# IsoPowerSupply.net
KiCad netlist of a schematic drawn in Altium Designer
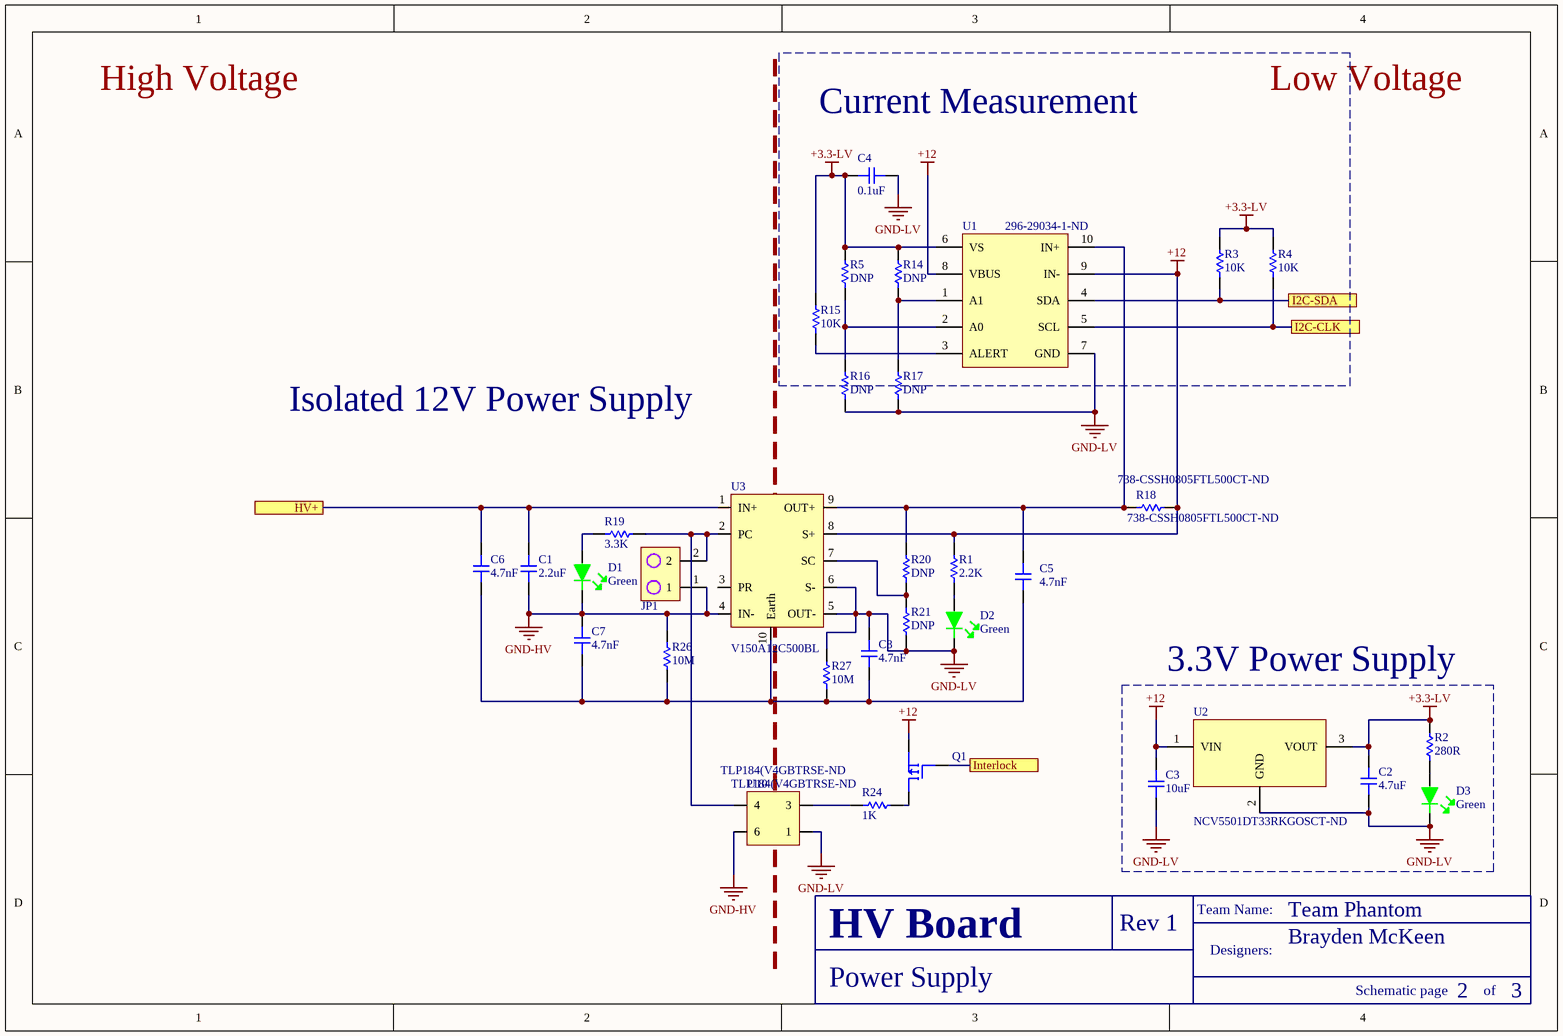
[diagram p0: IsoPowerSupply.SchDoc]

(export (version "E")
  (design (tool "Eeschema 10.0.6"))
  (components
    (comp (ref "C1")
      (value "2.2uF")
      (footprint "CAP-2220")
      (description "CAP CER 2.2UF 450V X6S 2220")
      (fields
        (field (name "MANUFACTURER") "TDK")
        (field (name "MANUFACTURER PART NUMBER") "C5750X6S2W225K250KA")
      )
      (libsource (lib "Capacitors") (part "2220-2.2uF-450V"))
    )
    (comp (ref "C2")
      (value "4.7uF")
      (footprint "CAP-0805")
      (description "CAP CER 4.7UF 16V X5R 0805")
      (fields
        (field (name "MANUFACTURER") "KEMET")
        (field (name "MANUFACTURER PART NUMBER") "C0805C475K4PACTU")
      )
      (libsource (lib "Capacitors") (part "0805-4.7uF-16V"))
    )
    (comp (ref "C3")
      (value "10uF")
      (footprint "CAP-1206")
      (description "CAP CER 10UF 50V X5R 1206")
      (fields
        (field (name "MANUFACTURER") "Murata")
        (field (name "MANUFACTURER PART NUMBER") "GRT31CR61H106ME01L")
      )
      (libsource (lib "Capacitors") (part "1206-10uF-50V"))
    )
    (comp (ref "C4")
      (value "0.1uF")
      (footprint "CAP-0805")
      (description "CAP CER 0.1UF 16V Y5V 0805")
      (fields
        (field (name "MANUFACTURER") "KEMET")
        (field (name "MANUFACTURER PART NUMBER") "C0805C104Z4VACTU")
      )
      (libsource (lib "Capacitors") (part "0805-0.1uF-16V"))
    )
    (comp (ref "C5")
      (value "4.7nF")
      (footprint "CAP-0805")
      (description "CAP CER 4700PF 250V X7R 0805")
      (libsource (lib "Capacitors") (part "0805-4.7nF-250V"))
    )
    (comp (ref "C6")
      (value "4.7nF")
      (footprint "CAP-0805")
      (description "CAP CER 4700PF 250V X7R 0805")
      (libsource (lib "Capacitors") (part "0805-4.7nF-250V"))
    )
    (comp (ref "C7")
      (value "4.7nF")
      (footprint "CAP-0805")
      (description "CAP CER 4700PF 250V X7R 0805")
      (libsource (lib "Capacitors") (part "0805-4.7nF-250V"))
    )
    (comp (ref "C8")
      (value "4.7nF")
      (footprint "CAP-0805")
      (description "CAP CER 4700PF 250V X7R 0805")
      (libsource (lib "Capacitors") (part "0805-4.7nF-250V"))
    )
    (comp (ref "D1")
      (value "Green")
      (footprint "LED-0603")
      (description "LED GREEN CLEAR 0603 SMD")
      (fields
        (field (name "MANUFACTURER") "Wurth Electronics")
        (field (name "MANUFACTURER PART NUMBER") "150060VS75000")
      )
      (libsource (lib "LEDs") (part "LED-Green"))
    )
    (comp (ref "D2")
      (value "Green")
      (footprint "LED-0603")
      (description "LED GREEN CLEAR 0603 SMD")
      (fields
        (field (name "MANUFACTURER") "Wurth Electronics")
        (field (name "MANUFACTURER PART NUMBER") "150060VS75000")
      )
      (libsource (lib "LEDs") (part "LED-Green"))
    )
    (comp (ref "D3")
      (value "Green")
      (footprint "LED-0603")
      (description "LED GREEN CLEAR 0603 SMD")
      (fields
        (field (name "MANUFACTURER") "Wurth Electronics")
        (field (name "MANUFACTURER PART NUMBER") "150060VS75000")
      )
      (libsource (lib "LEDs") (part "LED-Green"))
    )
    (comp (ref "JP1")
      (value "732-5315-ND")
      (footprint "2PIN-JP")
      (description "CONN HEADER VERT 2POS 2.54MM")
      (libsource (lib "Connectors") (part "2PIN-TEST"))
    )
    (comp (ref "Q1")
      (value "448-ISS17EP06LMXTSA1CT-ND")
      (footprint "SOT-23-3")
      (description "MOSFET P-CH 60V 300MA SOT23-3")
      (fields
        (field (name "MANUFACTURER") "ON Semiconductor")
        (field (name "MANUFACTURER PART NUMBER") "ISS17EP06LMXTSA1")
      )
      (libsource (lib "Transistors") (part "P-FET-60V-0.3A"))
    )
    (comp (ref "R1")
      (value "2.2K")
      (footprint "RES-0805")
      (description "RES SMD 2.2K OHM 1% 1/8W 0805")
      (fields
        (field (name "MANUFACTURER") "Yageo")
        (field (name "MANUFACTURER PART NUMBER") "RC0805FR-072K2L")
      )
      (libsource (lib "Resistors") (part "0805-2.2KR"))
    )
    (comp (ref "R2")
      (value "280R")
      (footprint "RES-0805")
      (description "RES SMD 280 OHM 1% 1/8W 0805")
      (fields
        (field (name "MANUFACTURER") "Yageo")
        (field (name "MANUFACTURER PART NUMBER") "RC0805FR-07280RL")
      )
      (libsource (lib "Resistors") (part "0805-280R"))
    )
    (comp (ref "R3")
      (value "10K")
      (footprint "RES-0805")
      (description "RES SMD 10K OHM 1% 1/8W 0805")
      (fields
        (field (name "MANUFACTURER") "Yageo")
        (field (name "MANUFACTURER PART NUMBER") "RC0805FR-0710KL")
      )
      (libsource (lib "Resistors") (part "0805-10KR"))
    )
    (comp (ref "R4")
      (value "10K")
      (footprint "RES-0805")
      (description "RES SMD 10K OHM 1% 1/8W 0805")
      (fields
        (field (name "MANUFACTURER") "Yageo")
        (field (name "MANUFACTURER PART NUMBER") "RC0805FR-0710KL")
      )
      (libsource (lib "Resistors") (part "0805-10KR"))
    )
    (comp (ref "R5") (value "DNP") (footprint "RES-0805") (libsource (lib "Resistors") (part "DNP")))
    (comp (ref "R14") (value "DNP") (footprint "RES-0805") (libsource (lib "Resistors") (part "DNP")))
    (comp (ref "R15")
      (value "10K")
      (footprint "RES-0805")
      (description "RES SMD 10K OHM 1% 1/8W 0805")
      (fields
        (field (name "MANUFACTURER") "Yageo")
        (field (name "MANUFACTURER PART NUMBER") "RC0805FR-0710KL")
      )
      (libsource (lib "Resistors") (part "0805-10KR"))
    )
    (comp (ref "R16") (value "DNP") (footprint "RES-0805") (libsource (lib "Resistors") (part "DNP")))
    (comp (ref "R17") (value "DNP") (footprint "RES-0805") (libsource (lib "Resistors") (part "DNP")))
    (comp (ref "R18")
      (value "738-CSSH0805FTL500CT-ND")
      (footprint "RES-0805")
      (description "RES SHUNT, 0805, 0.0005 OHM, 1%,")
      (fields (field (name "SUPPLIER PART NUMBER 1") "738-CSSH0805FTL500CT-ND"))
      (libsource (lib "Resistors") (part "0805-0.0005R"))
    )
    (comp (ref "R19")
      (value "3.3K")
      (footprint "RES-0805")
      (description "RES SMD 3.3K OHM 1% 1/8W 0805")
      (fields
        (field (name "MANUFACTURER") "TE Connectivity")
        (field (name "MANUFACTURER PART NUMBER") "CRGCQ0805F3K3")
      )
      (libsource (lib "Resistors") (part "0805-3.3KR"))
    )
    (comp (ref "R20") (value "DNP") (footprint "RES-0805") (libsource (lib "Resistors") (part "DNP")))
    (comp (ref "R21") (value "DNP") (footprint "RES-0805") (libsource (lib "Resistors") (part "DNP")))
    (comp (ref "R24")
      (value "1K")
      (footprint "RES-0805")
      (description "RES SMD 1K OHM 1% 1/8W 0805")
      (fields
        (field (name "MANUFACTURER") "Yageo")
        (field (name "MANUFACTURER PART NUMBER") "RC0805FR-071KL")
      )
      (libsource (lib "Resistors") (part "0805-1KR"))
    )
    (comp (ref "R26")
      (value "10M")
      (footprint "RES-0805")
      (description "RES SMD 10M OHM 1% 1/8W 0805")
      (libsource (lib "Resistors") (part "0805-10MR"))
    )
    (comp (ref "R27")
      (value "10M")
      (footprint "RES-0805")
      (description "RES SMD 10M OHM 1% 1/8W 0805")
      (libsource (lib "Resistors") (part "0805-10MR"))
    )
    (comp (ref "U1")
      (value "296-29034-1-ND")
      (footprint "10MSOP")
      (description "IC MONITOR PWR/CURR BIDIR 10MSOP")
      (fields
        (field (name "MANUFACTURER") "Texas Instruments")
        (field (name "MANUFACTURER PART NUMBER") "INA226AIDGSR")
      )
      (libsource (lib "ICs") (part "PWR Monitor"))
    )
    (comp (ref "U2")
      (value "NCV5501DT33RKGOSCT-ND")
      (footprint "DPAK-TO252")
      (description "IC REG LINEAR 3.3V 500MA DPAK")
      (fields
        (field (name "MANUFACTURER") "ON Semiconductor")
        (field (name "MANUFACTURER PART NUMBER") "NCV5501DT33RKG")
      )
      (libsource (lib "Power") (part "LDO-3.3V-500mA"))
    )
    (comp (ref "U3")
      (value "V150A12C500BL")
      (footprint "DCDC-200V-12V-500W")
      (description "DC DC CONVERTER 12V 500W")
      (fields (field (name "MANUFACTURER") "Vicor"))
      (libsource (lib "Power") (part "DCDC200V-12V"))
    )
    (comp (ref "U10")
      (value "TLP184(V4GBTRSE-ND")
      (footprint "Photocoupler")
      (description "X36 PB-F PHOTOCOUPLER SO6 ROHS T")
      (fields (field (name "SUPPLIER PART NUMBER 1") "TLP184(V4GBTRSE-ND"))
      (libsource (lib "Misc") (part "Photocoupler"))
    )
  )
  (nets
    (net (code "1") (name "+3.3-LV") (class "Default")
      (node (ref "C2") (pin "2") (pinfunction "2_2") (pintype "passive"))
      (node (ref "C4") (pin "1") (pinfunction "1_1") (pintype "passive"))
      (node (ref "R14") (pin "2") (pinfunction "2_2") (pintype "passive"))
      (node (ref "R15") (pin "2") (pinfunction "2_2") (pintype "passive"))
      (node (ref "R2") (pin "2") (pinfunction "2_2") (pintype "passive"))
      (node (ref "R3") (pin "2") (pinfunction "2_2") (pintype "passive"))
      (node (ref "R4") (pin "2") (pinfunction "2_2") (pintype "passive"))
      (node (ref "R5") (pin "2") (pinfunction "2_2") (pintype "passive"))
      (node (ref "U1") (pin "6") (pinfunction "VS_6") (pintype "passive"))
      (node (ref "U2") (pin "3") (pinfunction "VOUT_3") (pintype "passive"))
    )
    (net (code "2") (name "+12") (class "Default")
      (node (ref "C3") (pin "2") (pinfunction "2_2") (pintype "passive"))
      (node (ref "Q1") (pin "2") (pinfunction "2_2") (pintype "passive"))
      (node (ref "R1") (pin "2") (pinfunction "2_2") (pintype "passive"))
      (node (ref "R18") (pin "2") (pinfunction "2_2") (pintype "passive"))
      (node (ref "U1") (pin "8") (pinfunction "VBUS_8") (pintype "passive"))
      (node (ref "U1") (pin "9") (pinfunction "IN-_9") (pintype "passive"))
      (node (ref "U2") (pin "1") (pinfunction "VIN_1") (pintype "passive"))
      (node (ref "U3") (pin "8") (pinfunction "S+_8") (pintype "passive"))
    )
    (net (code "3") (name "/HV+") (class "Default")
      (node (ref "C1") (pin "2") (pinfunction "2_2") (pintype "passive"))
      (node (ref "C6") (pin "2") (pinfunction "2_2") (pintype "passive"))
      (node (ref "U3") (pin "1") (pinfunction "IN+_1") (pintype "passive"))
    )
    (net (code "4") (name "/I2C-CLK") (class "Default")
      (node (ref "R4") (pin "1") (pinfunction "1_1") (pintype "passive"))
      (node (ref "U1") (pin "5") (pinfunction "SCL_5") (pintype "passive"))
    )
    (net (code "5") (name "/I2C-SDA") (class "Default")
      (node (ref "R3") (pin "1") (pinfunction "1_1") (pintype "passive"))
      (node (ref "U1") (pin "4") (pinfunction "SDA_4") (pintype "passive"))
    )
    (net (code "6") (name "/Interlock") (class "Default")
      (node (ref "Q1") (pin "1") (pinfunction "1_1") (pintype "passive"))
    )
    (net (code "7") (name "GND-HV") (class "Default")
      (node (ref "C1") (pin "1") (pinfunction "1_1") (pintype "passive"))
      (node (ref "C7") (pin "2") (pinfunction "2_2") (pintype "passive"))
      (node (ref "D1") (pin "2") (pinfunction "2_2") (pintype "passive"))
      (node (ref "JP1") (pin "1") (pinfunction "1_1") (pintype "passive"))
      (node (ref "R26") (pin "1") (pinfunction "1_1") (pintype "passive"))
      (node (ref "U10") (pin "6") (pinfunction "6_6") (pintype "passive"))
      (node (ref "U3") (pin "4") (pinfunction "IN-_4") (pintype "passive"))
    )
    (net (code "8") (name "GND-LV") (class "Default")
      (node (ref "C2") (pin "1") (pinfunction "1_1") (pintype "passive"))
      (node (ref "C3") (pin "1") (pinfunction "1_1") (pintype "passive"))
      (node (ref "C4") (pin "2") (pinfunction "2_2") (pintype "passive"))
      (node (ref "C8") (pin "2") (pinfunction "2_2") (pintype "passive"))
      (node (ref "D2") (pin "2") (pinfunction "2_2") (pintype "passive"))
      (node (ref "D3") (pin "2") (pinfunction "2_2") (pintype "passive"))
      (node (ref "R16") (pin "1") (pinfunction "1_1") (pintype "passive"))
      (node (ref "R17") (pin "1") (pinfunction "1_1") (pintype "passive"))
      (node (ref "R21") (pin "2") (pinfunction "2_2") (pintype "passive"))
      (node (ref "R27") (pin "2") (pinfunction "2_2") (pintype "passive"))
      (node (ref "U1") (pin "7") (pinfunction "GND_7") (pintype "passive"))
      (node (ref "U10") (pin "1") (pinfunction "1_1") (pintype "passive"))
      (node (ref "U2") (pin "2") (pinfunction "GND_2") (pintype "passive"))
      (node (ref "U3") (pin "5") (pinfunction "OUT-_5") (pintype "passive"))
      (node (ref "U3") (pin "6") (pinfunction "S-_6") (pintype "passive"))
    )
    (net (code "9") (name "Net-(D1-Pad1)") (class "Default")
      (node (ref "D1") (pin "1") (pinfunction "1_1") (pintype "passive"))
      (node (ref "R19") (pin "1") (pinfunction "1_1") (pintype "passive"))
    )
    (net (code "10") (name "Net-(D2-Pad1)") (class "Default")
      (node (ref "D2") (pin "1") (pinfunction "1_1") (pintype "passive"))
      (node (ref "R1") (pin "1") (pinfunction "1_1") (pintype "passive"))
    )
    (net (code "11") (name "Net-(D3-Pad1)") (class "Default")
      (node (ref "D3") (pin "1") (pinfunction "1_1") (pintype "passive"))
      (node (ref "R2") (pin "1") (pinfunction "1_1") (pintype "passive"))
    )
    (net (code "12") (name "Net-(Q1-Pad3)") (class "Default")
      (node (ref "Q1") (pin "3") (pinfunction "3_3") (pintype "passive"))
      (node (ref "R24") (pin "2") (pinfunction "2_2") (pintype "passive"))
    )
    (net (code "13") (name "Net-(R24-Pad1)") (class "Default")
      (node (ref "R24") (pin "1") (pinfunction "1_1") (pintype "passive"))
      (node (ref "U10") (pin "3") (pinfunction "3_3") (pintype "passive"))
    )
    (net (code "14") (name "Net-(U1-A0)") (class "Default")
      (node (ref "R16") (pin "2") (pinfunction "2_2") (pintype "passive"))
      (node (ref "R5") (pin "1") (pinfunction "1_1") (pintype "passive"))
      (node (ref "U1") (pin "2") (pinfunction "A0_2") (pintype "passive"))
    )
    (net (code "15") (name "Net-(U1-A1)") (class "Default")
      (node (ref "R14") (pin "1") (pinfunction "1_1") (pintype "passive"))
      (node (ref "R17") (pin "2") (pinfunction "2_2") (pintype "passive"))
      (node (ref "U1") (pin "1") (pinfunction "A1_1") (pintype "passive"))
    )
    (net (code "16") (name "Net-(U1-ALERT)") (class "Default")
      (node (ref "R15") (pin "1") (pinfunction "1_1") (pintype "passive"))
      (node (ref "U1") (pin "3") (pinfunction "ALERT_3") (pintype "passive"))
    )
    (net (code "17") (name "Net-(U1-IN+)") (class "Default")
      (node (ref "C5") (pin "2") (pinfunction "2_2") (pintype "passive"))
      (node (ref "R18") (pin "1") (pinfunction "1_1") (pintype "passive"))
      (node (ref "R20") (pin "2") (pinfunction "2_2") (pintype "passive"))
      (node (ref "U1") (pin "10") (pinfunction "IN+_10") (pintype "passive"))
      (node (ref "U3") (pin "9") (pinfunction "OUT+_9") (pintype "passive"))
    )
    (net (code "18") (name "Net-(U3-Earth)") (class "Default")
      (node (ref "C5") (pin "1") (pinfunction "1_1") (pintype "passive"))
      (node (ref "C6") (pin "1") (pinfunction "1_1") (pintype "passive"))
      (node (ref "C7") (pin "1") (pinfunction "1_1") (pintype "passive"))
      (node (ref "C8") (pin "1") (pinfunction "1_1") (pintype "passive"))
      (node (ref "R26") (pin "2") (pinfunction "2_2") (pintype "passive"))
      (node (ref "R27") (pin "1") (pinfunction "1_1") (pintype "passive"))
      (node (ref "U3") (pin "10") (pinfunction "Earth_10") (pintype "passive"))
    )
    (net (code "19") (name "Net-(U3-PC)") (class "Default")
      (node (ref "JP1") (pin "2") (pinfunction "2_2") (pintype "passive"))
      (node (ref "R19") (pin "2") (pinfunction "2_2") (pintype "passive"))
      (node (ref "U10") (pin "4") (pinfunction "4_4") (pintype "passive"))
      (node (ref "U3") (pin "2") (pinfunction "PC_2") (pintype "passive"))
    )
    (net (code "20") (name "Net-(U3-SC)") (class "Default")
      (node (ref "R20") (pin "1") (pinfunction "1_1") (pintype "passive"))
      (node (ref "R21") (pin "1") (pinfunction "1_1") (pintype "passive"))
      (node (ref "U3") (pin "7") (pinfunction "SC_7") (pintype "passive"))
    )
    (net (code "21") (name "unconnected-(U3-PR-Pad3)") (class "Default")
      (node (ref "U3") (pin "3") (pinfunction "PR_3") (pintype "passive"))
    )
  )
)
